# Pan_Tilt_Stepper_Control.net
KiCad netlist of a schematic drawn in Altium Designer
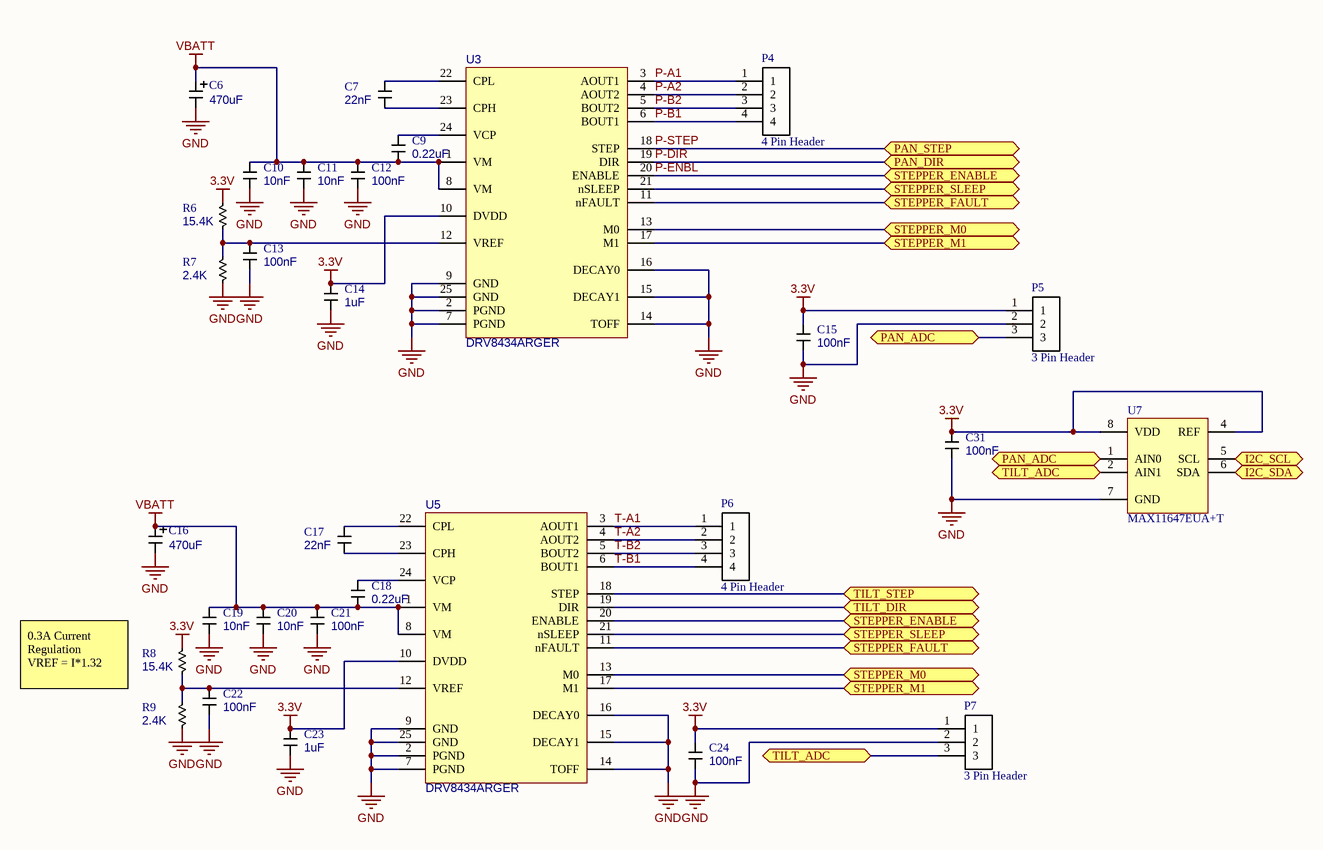
[diagram p0: Pan & Tilt Stepper Control.SchDoc]

(export (version "E")
  (design (tool "Eeschema 10.0.6"))
  (components
    (comp (ref "C6")
      (value "F")
      (footprint "Panasonic EEE-FT1E471AP")
      (description "Polarized Capacitor")
      (fields
        (field (name "MANUFACTURER") "Panasonic Electronic Components")
        (field (name "MANUFACTURER PART NUMBER") "EEE-FT1E471AP")
        (field (name "CAPACITANCE") "470uF")
      )
      (libsource (lib "Rigby Electronics Schematic Library") (part "Capacitor Polarized"))
    )
    (comp (ref "C7")
      (value "F")
      (footprint "C0805")
      (description "Capacitor")
      (fields
        (field (name "MANUFACTURER") "TDK Corporation")
        (field (name "MANUFACTURER PART NUMBER") "CGA4J3X7R2E223K125AA")
        (field (name "CAPACITANCE") "22nF")
      )
      (libsource (lib "Rigby Electronics Schematic Library") (part "Capacitor"))
    )
    (comp (ref "C9")
      (value "F")
      (footprint "C0805")
      (description "Capacitor")
      (fields
        (field (name "MANUFACTURER") "KEMET")
        (field (name "MANUFACTURER PART NUMBER") "C0805C224K5RAC7800")
        (field (name "CAPACITANCE") "0.22uF")
      )
      (libsource (lib "Rigby Electronics Schematic Library") (part "Capacitor"))
    )
    (comp (ref "C10")
      (value "F")
      (footprint "C0805")
      (description "Capacitor")
      (fields
        (field (name "MANUFACTURER") "YAGEO")
        (field (name "MANUFACTURER PART NUMBER") "CC0805KRX7R9BB103")
        (field (name "CAPACITANCE") "10nF")
      )
      (libsource (lib "Rigby Electronics Schematic Library") (part "Capacitor"))
    )
    (comp (ref "C11")
      (value "F")
      (footprint "C0805")
      (description "Capacitor")
      (fields
        (field (name "MANUFACTURER") "YAGEO")
        (field (name "MANUFACTURER PART NUMBER") "CC0805KRX7R9BB103")
        (field (name "CAPACITANCE") "10nF")
      )
      (libsource (lib "Rigby Electronics Schematic Library") (part "Capacitor"))
    )
    (comp (ref "C12")
      (value "F")
      (footprint "C0805")
      (description "Capacitor")
      (fields
        (field (name "MANUFACTURER") "Samsung Electro-Mechanics")
        (field (name "MANUFACTURER PART NUMBER") "CL21B104KBCNNNC")
        (field (name "CAPACITANCE") "100nF")
      )
      (libsource (lib "Rigby Electronics Schematic Library") (part "Capacitor"))
    )
    (comp (ref "C13")
      (value "F")
      (footprint "C0805")
      (description "Capacitor")
      (fields
        (field (name "MANUFACTURER") "Samsung Electro-Mechanics")
        (field (name "MANUFACTURER PART NUMBER") "CL21B104KBCNNNC")
        (field (name "CAPACITANCE") "100nF")
      )
      (libsource (lib "Rigby Electronics Schematic Library") (part "Capacitor"))
    )
    (comp (ref "C14")
      (value "F")
      (footprint "C0805")
      (description "Capacitor")
      (fields
        (field (name "MANUFACTURER") "Samsung Electro-Mechanics")
        (field (name "MANUFACTURER PART NUMBER") "CL21B105KAFNNNE")
        (field (name "CAPACITANCE") "1uF")
      )
      (libsource (lib "Rigby Electronics Schematic Library") (part "Capacitor"))
    )
    (comp (ref "C15")
      (value "F")
      (footprint "C0805")
      (description "Capacitor")
      (fields
        (field (name "MANUFACTURER") "Samsung Electro-Mechanics")
        (field (name "MANUFACTURER PART NUMBER") "CL21B104KBCNNNC")
        (field (name "CAPACITANCE") "100nF")
      )
      (libsource (lib "Rigby Electronics Schematic Library") (part "Capacitor"))
    )
    (comp (ref "C16")
      (value "F")
      (footprint "Panasonic EEE-FT1E471AP")
      (description "Polarized Capacitor")
      (fields
        (field (name "MANUFACTURER") "Panasonic Electronic Components")
        (field (name "MANUFACTURER PART NUMBER") "EEE-FT1E471AP")
        (field (name "CAPACITANCE") "470uF")
      )
      (libsource (lib "Rigby Electronics Schematic Library") (part "Capacitor Polarized"))
    )
    (comp (ref "C17")
      (value "F")
      (footprint "C0805")
      (description "Capacitor")
      (fields
        (field (name "MANUFACTURER") "TDK Corporation")
        (field (name "MANUFACTURER PART NUMBER") "CGA4J3X7R2E223K125AA")
        (field (name "CAPACITANCE") "22nF")
      )
      (libsource (lib "Rigby Electronics Schematic Library") (part "Capacitor"))
    )
    (comp (ref "C18")
      (value "F")
      (footprint "C0805")
      (description "Capacitor")
      (fields
        (field (name "MANUFACTURER") "KEMET")
        (field (name "MANUFACTURER PART NUMBER") "C0805C224K5RAC7800")
        (field (name "CAPACITANCE") "0.22uF")
      )
      (libsource (lib "Rigby Electronics Schematic Library") (part "Capacitor"))
    )
    (comp (ref "C19")
      (value "F")
      (footprint "C0805")
      (description "Capacitor")
      (fields
        (field (name "MANUFACTURER") "YAGEO")
        (field (name "MANUFACTURER PART NUMBER") "CC0805KRX7R9BB103")
        (field (name "CAPACITANCE") "10nF")
      )
      (libsource (lib "Rigby Electronics Schematic Library") (part "Capacitor"))
    )
    (comp (ref "C20")
      (value "F")
      (footprint "C0805")
      (description "Capacitor")
      (fields
        (field (name "MANUFACTURER") "YAGEO")
        (field (name "MANUFACTURER PART NUMBER") "CC0805KRX7R9BB103")
        (field (name "CAPACITANCE") "10nF")
      )
      (libsource (lib "Rigby Electronics Schematic Library") (part "Capacitor"))
    )
    (comp (ref "C21")
      (value "F")
      (footprint "C0805")
      (description "Capacitor")
      (fields
        (field (name "MANUFACTURER") "Samsung Electro-Mechanics")
        (field (name "MANUFACTURER PART NUMBER") "CL21B104KBCNNNC")
        (field (name "CAPACITANCE") "100nF")
      )
      (libsource (lib "Rigby Electronics Schematic Library") (part "Capacitor"))
    )
    (comp (ref "C22")
      (value "F")
      (footprint "C0805")
      (description "Capacitor")
      (fields
        (field (name "MANUFACTURER") "Samsung Electro-Mechanics")
        (field (name "MANUFACTURER PART NUMBER") "CL21B104KBCNNNC")
        (field (name "CAPACITANCE") "100nF")
      )
      (libsource (lib "Rigby Electronics Schematic Library") (part "Capacitor"))
    )
    (comp (ref "C23")
      (value "F")
      (footprint "C0805")
      (description "Capacitor")
      (fields
        (field (name "MANUFACTURER") "Samsung Electro-Mechanics")
        (field (name "MANUFACTURER PART NUMBER") "CL21B105KAFNNNE")
        (field (name "CAPACITANCE") "1uF")
      )
      (libsource (lib "Rigby Electronics Schematic Library") (part "Capacitor"))
    )
    (comp (ref "C24")
      (value "F")
      (footprint "C0805")
      (description "Capacitor")
      (fields
        (field (name "MANUFACTURER") "Samsung Electro-Mechanics")
        (field (name "MANUFACTURER PART NUMBER") "CL21B104KBCNNNC")
        (field (name "CAPACITANCE") "100nF")
      )
      (libsource (lib "Rigby Electronics Schematic Library") (part "Capacitor"))
    )
    (comp (ref "C31")
      (value "F")
      (footprint "C0805")
      (description "Capacitor")
      (fields
        (field (name "MANUFACTURER") "Samsung Electro-Mechanics")
        (field (name "MANUFACTURER PART NUMBER") "CL21B104KBCNNNC")
        (field (name "CAPACITANCE") "100nF")
      )
      (libsource (lib "Rigby Electronics Schematic Library") (part "Capacitor"))
    )
    (comp (ref "P4")
      (value "4 Pin Header")
      (footprint "B4B-XH-A")
      (fields (field (name "MANUFACTURER") "JST") (field (name "MANUFACTURER PART NUMBER") "B4B-XH-2"))
      (libsource (lib "Rigby Electronics Schematic Library") (part "Header 4"))
    )
    (comp (ref "P5")
      (value "3 Pin Header")
      (footprint "B3B-XH-A")
      (fields
        (field (name "MANUFACTURER") "JST Sales America Inc.")
        (field (name "MANUFACTURER PART NUMBER") "B3B-XH-A")
      )
      (libsource (lib "Rigby Electronics Library") (part "Header 3"))
    )
    (comp (ref "P6")
      (value "4 Pin Header")
      (footprint "B4B-XH-A")
      (fields (field (name "MANUFACTURER") "JST") (field (name "MANUFACTURER PART NUMBER") "B4B-XH-2"))
      (libsource (lib "Rigby Electronics Schematic Library") (part "Header 4"))
    )
    (comp (ref "P7")
      (value "3 Pin Header")
      (footprint "B3B-XH-A")
      (fields
        (field (name "MANUFACTURER") "JST Sales America Inc.")
        (field (name "MANUFACTURER PART NUMBER") "B3B-XH-A")
      )
      (libsource (lib "Rigby Electronics Library") (part "Header 3"))
    )
    (comp (ref "R6")
      (value "330Ω")
      (footprint "R0805")
      (description "Standard Resistor")
      (fields
        (field (name "MANUFACTURER") "Vishay Dale")
        (field (name "MANUFACTURER PART NUMBER") "CRCW080515K4FKEA")
        (field (name "RESISTANCE") "15.4K")
      )
      (libsource (lib "Rigby Electronics Schematic Library") (part "Resistor"))
    )
    (comp (ref "R7")
      (value "330Ω")
      (footprint "R0805")
      (description "Standard Resistor")
      (fields
        (field (name "MANUFACTURER") "Vishay Dale")
        (field (name "MANUFACTURER PART NUMBER") "CRCW08052K10FKEA")
        (field (name "RESISTANCE") "2.4K")
      )
      (libsource (lib "Rigby Electronics Schematic Library") (part "Resistor"))
    )
    (comp (ref "R8")
      (value "330Ω")
      (footprint "R0805")
      (description "Standard Resistor")
      (fields
        (field (name "MANUFACTURER") "Vishay Dale")
        (field (name "MANUFACTURER PART NUMBER") "CRCW080515K4FKEA")
        (field (name "RESISTANCE") "15.4K")
      )
      (libsource (lib "Rigby Electronics Schematic Library") (part "Resistor"))
    )
    (comp (ref "R9")
      (value "330Ω")
      (footprint "R0805")
      (description "Standard Resistor")
      (fields
        (field (name "MANUFACTURER") "Vishay Dale")
        (field (name "MANUFACTURER PART NUMBER") "CRCW08052K10FKEA")
        (field (name "RESISTANCE") "2.4K")
      )
      (libsource (lib "Rigby Electronics Schematic Library") (part "Resistor"))
    )
    (comp (ref "U3")
      (value "DRV8434ARGER")
      (footprint "DRV8434ARGER")
      (description "Bipolar Motor Driver NMOS Step/Direction 24-VQFN (4x4)")
      (fields (field (name "MANUFACTURER") "Texas Instruments"))
      (libsource (lib "Rigby Electronics Schematic Library") (part "DRV8434ARGER"))
    )
    (comp (ref "U5")
      (value "DRV8434ARGER")
      (footprint "DRV8434ARGER")
      (description "Bipolar Motor Driver NMOS Step/Direction 24-VQFN (4x4)")
      (fields (field (name "MANUFACTURER") "Texas Instruments"))
      (libsource (lib "Rigby Electronics Schematic Library") (part "DRV8434ARGER"))
    )
    (comp (ref "U7")
      (value "MAX11647EUA+T")
      (footprint "MAX11647EUA+T")
      (description "10 Bit Analog to Digital Converter 1, 2 Input 1 SAR 8-uMAX/uSOP")
      (fields (field (name "MANUFACTURER") "Analog Devices Inc./Maxim Integrated"))
      (libsource (lib "Rigby Electronics Schematic Library") (part "MAX11647EUA+T"))
    )
  )
  (nets
    (net (code "1") (name "/I2C_SCL") (class "Default")
      (node (ref "U7") (pin "5") (pinfunction "SCL_5") (pintype "passive"))
    )
    (net (code "2") (name "/I2C_SDA") (class "Default")
      (node (ref "U7") (pin "6") (pinfunction "SDA_6") (pintype "passive"))
    )
    (net (code "3") (name "/P-A1") (class "Default")
      (node (ref "P4") (pin "1") (pinfunction "1_1") (pintype "passive"))
      (node (ref "U3") (pin "3") (pinfunction "AOUT1_3") (pintype "passive"))
    )
    (net (code "4") (name "/P-A2") (class "Default")
      (node (ref "P4") (pin "2") (pinfunction "2_2") (pintype "passive"))
      (node (ref "U3") (pin "4") (pinfunction "AOUT2_4") (pintype "passive"))
    )
    (net (code "5") (name "/P-B1") (class "Default")
      (node (ref "P4") (pin "4") (pinfunction "4_4") (pintype "passive"))
      (node (ref "U3") (pin "6") (pinfunction "BOUT1_6") (pintype "passive"))
    )
    (net (code "6") (name "/P-B2") (class "Default")
      (node (ref "P4") (pin "3") (pinfunction "3_3") (pintype "passive"))
      (node (ref "U3") (pin "5") (pinfunction "BOUT2_5") (pintype "passive"))
    )
    (net (code "7") (name "/P-DIR") (class "Default")
      (node (ref "U3") (pin "19") (pinfunction "DIR_19") (pintype "passive"))
    )
    (net (code "8") (name "/P-ENBL") (class "Default")
      (node (ref "U3") (pin "20") (pinfunction "ENABLE_20") (pintype "passive"))
      (node (ref "U5") (pin "20") (pinfunction "ENABLE_20") (pintype "passive"))
    )
    (net (code "9") (name "/P-STEP") (class "Default")
      (node (ref "U3") (pin "18") (pinfunction "STEP_18") (pintype "passive"))
    )
    (net (code "10") (name "/PAN_ADC") (class "Default")
      (node (ref "P5") (pin "3") (pinfunction "3_3") (pintype "passive"))
      (node (ref "U7") (pin "1") (pinfunction "AIN0_1") (pintype "passive"))
    )
    (net (code "11") (name "/STEPPER_FAULT") (class "Default")
      (node (ref "U3") (pin "11") (pinfunction "nFAULT_11") (pintype "passive"))
      (node (ref "U5") (pin "11") (pinfunction "nFAULT_11") (pintype "passive"))
    )
    (net (code "12") (name "/STEPPER_M0") (class "Default")
      (node (ref "U3") (pin "13") (pinfunction "M0_13") (pintype "passive"))
      (node (ref "U5") (pin "13") (pinfunction "M0_13") (pintype "passive"))
    )
    (net (code "13") (name "/STEPPER_M1") (class "Default")
      (node (ref "U3") (pin "17") (pinfunction "M1_17") (pintype "passive"))
      (node (ref "U5") (pin "17") (pinfunction "M1_17") (pintype "passive"))
    )
    (net (code "14") (name "/STEPPER_SLEEP") (class "Default")
      (node (ref "U3") (pin "21") (pinfunction "nSLEEP_21") (pintype "passive"))
      (node (ref "U5") (pin "21") (pinfunction "nSLEEP_21") (pintype "passive"))
    )
    (net (code "15") (name "/T-A1") (class "Default")
      (node (ref "P6") (pin "1") (pinfunction "1_1") (pintype "passive"))
      (node (ref "U5") (pin "3") (pinfunction "AOUT1_3") (pintype "passive"))
    )
    (net (code "16") (name "/T-A2") (class "Default")
      (node (ref "P6") (pin "2") (pinfunction "2_2") (pintype "passive"))
      (node (ref "U5") (pin "4") (pinfunction "AOUT2_4") (pintype "passive"))
    )
    (net (code "17") (name "/T-B1") (class "Default")
      (node (ref "P6") (pin "4") (pinfunction "4_4") (pintype "passive"))
      (node (ref "U5") (pin "6") (pinfunction "BOUT1_6") (pintype "passive"))
    )
    (net (code "18") (name "/T-B2") (class "Default")
      (node (ref "P6") (pin "3") (pinfunction "3_3") (pintype "passive"))
      (node (ref "U5") (pin "5") (pinfunction "BOUT2_5") (pintype "passive"))
    )
    (net (code "19") (name "/TILT_ADC") (class "Default")
      (node (ref "P7") (pin "3") (pinfunction "3_3") (pintype "passive"))
      (node (ref "U7") (pin "2") (pinfunction "AIN1_2") (pintype "passive"))
    )
    (net (code "20") (name "/TILT_DIR") (class "Default")
      (node (ref "U5") (pin "19") (pinfunction "DIR_19") (pintype "passive"))
    )
    (net (code "21") (name "/TILT_STEP") (class "Default")
      (node (ref "U5") (pin "18") (pinfunction "STEP_18") (pintype "passive"))
    )
    (net (code "22") (name "3.3V") (class "Default")
      (node (ref "C14") (pin "1") (pinfunction "1_1") (pintype "passive"))
      (node (ref "C15") (pin "1") (pinfunction "1_1") (pintype "passive"))
      (node (ref "C23") (pin "1") (pinfunction "1_1") (pintype "passive"))
      (node (ref "C24") (pin "1") (pinfunction "1_1") (pintype "passive"))
      (node (ref "C31") (pin "1") (pinfunction "1_1") (pintype "passive"))
      (node (ref "P5") (pin "1") (pinfunction "1_1") (pintype "passive"))
      (node (ref "P7") (pin "1") (pinfunction "1_1") (pintype "passive"))
      (node (ref "R6") (pin "2") (pinfunction "2_2") (pintype "passive"))
      (node (ref "R8") (pin "2") (pinfunction "2_2") (pintype "passive"))
      (node (ref "U3") (pin "10") (pinfunction "DVDD_10") (pintype "passive"))
      (node (ref "U5") (pin "10") (pinfunction "DVDD_10") (pintype "passive"))
      (node (ref "U7") (pin "4") (pinfunction "REF_4") (pintype "passive"))
      (node (ref "U7") (pin "8") (pinfunction "VDD_8") (pintype "passive"))
    )
    (net (code "23") (name "GND") (class "Default")
      (node (ref "C10") (pin "2") (pinfunction "2_2") (pintype "passive"))
      (node (ref "C11") (pin "2") (pinfunction "2_2") (pintype "passive"))
      (node (ref "C12") (pin "2") (pinfunction "2_2") (pintype "passive"))
      (node (ref "C13") (pin "2") (pinfunction "2_2") (pintype "passive"))
      (node (ref "C14") (pin "2") (pinfunction "2_2") (pintype "passive"))
      (node (ref "C15") (pin "2") (pinfunction "2_2") (pintype "passive"))
      (node (ref "C16") (pin "2") (pinfunction "2_2") (pintype "passive"))
      (node (ref "C19") (pin "2") (pinfunction "2_2") (pintype "passive"))
      (node (ref "C20") (pin "2") (pinfunction "2_2") (pintype "passive"))
      (node (ref "C21") (pin "2") (pinfunction "2_2") (pintype "passive"))
      (node (ref "C22") (pin "2") (pinfunction "2_2") (pintype "passive"))
      (node (ref "C23") (pin "2") (pinfunction "2_2") (pintype "passive"))
      (node (ref "C24") (pin "2") (pinfunction "2_2") (pintype "passive"))
      (node (ref "C31") (pin "2") (pinfunction "2_2") (pintype "passive"))
      (node (ref "C6") (pin "2") (pinfunction "2_2") (pintype "passive"))
      (node (ref "P5") (pin "2") (pinfunction "2_2") (pintype "passive"))
      (node (ref "P7") (pin "2") (pinfunction "2_2") (pintype "passive"))
      (node (ref "R7") (pin "1") (pinfunction "1_1") (pintype "passive"))
      (node (ref "R9") (pin "1") (pinfunction "1_1") (pintype "passive"))
      (node (ref "U3") (pin "14") (pinfunction "TOFF_14") (pintype "passive"))
      (node (ref "U3") (pin "15") (pinfunction "DECAY1_15") (pintype "passive"))
      (node (ref "U3") (pin "16") (pinfunction "DECAY0_16") (pintype "passive"))
      (node (ref "U3") (pin "2") (pinfunction "PGND_2") (pintype "passive"))
      (node (ref "U3") (pin "25") (pinfunction "GND_25") (pintype "passive"))
      (node (ref "U3") (pin "7") (pinfunction "PGND_7") (pintype "passive"))
      (node (ref "U3") (pin "9") (pinfunction "GND_9") (pintype "passive"))
      (node (ref "U5") (pin "14") (pinfunction "TOFF_14") (pintype "passive"))
      (node (ref "U5") (pin "15") (pinfunction "DECAY1_15") (pintype "passive"))
      (node (ref "U5") (pin "16") (pinfunction "DECAY0_16") (pintype "passive"))
      (node (ref "U5") (pin "2") (pinfunction "PGND_2") (pintype "passive"))
      (node (ref "U5") (pin "25") (pinfunction "GND_25") (pintype "passive"))
      (node (ref "U5") (pin "7") (pinfunction "PGND_7") (pintype "passive"))
      (node (ref "U5") (pin "9") (pinfunction "GND_9") (pintype "passive"))
      (node (ref "U7") (pin "7") (pinfunction "GND_7") (pintype "passive"))
    )
    (net (code "24") (name "Net-(U3-CPH)") (class "Default")
      (node (ref "C7") (pin "2") (pinfunction "2_2") (pintype "passive"))
      (node (ref "U3") (pin "23") (pinfunction "CPH_23") (pintype "passive"))
    )
    (net (code "25") (name "Net-(U3-CPL)") (class "Default")
      (node (ref "C7") (pin "1") (pinfunction "1_1") (pintype "passive"))
      (node (ref "U3") (pin "22") (pinfunction "CPL_22") (pintype "passive"))
    )
    (net (code "26") (name "Net-(U3-VCP)") (class "Default")
      (node (ref "C9") (pin "1") (pinfunction "1_1") (pintype "passive"))
      (node (ref "U3") (pin "24") (pinfunction "VCP_24") (pintype "passive"))
    )
    (net (code "27") (name "Net-(U3-VREF)") (class "Default")
      (node (ref "C13") (pin "1") (pinfunction "1_1") (pintype "passive"))
      (node (ref "R6") (pin "1") (pinfunction "1_1") (pintype "passive"))
      (node (ref "R7") (pin "2") (pinfunction "2_2") (pintype "passive"))
      (node (ref "U3") (pin "12") (pinfunction "VREF_12") (pintype "passive"))
    )
    (net (code "28") (name "Net-(U5-CPH)") (class "Default")
      (node (ref "C17") (pin "2") (pinfunction "2_2") (pintype "passive"))
      (node (ref "U5") (pin "23") (pinfunction "CPH_23") (pintype "passive"))
    )
    (net (code "29") (name "Net-(U5-CPL)") (class "Default")
      (node (ref "C17") (pin "1") (pinfunction "1_1") (pintype "passive"))
      (node (ref "U5") (pin "22") (pinfunction "CPL_22") (pintype "passive"))
    )
    (net (code "30") (name "Net-(U5-VCP)") (class "Default")
      (node (ref "C18") (pin "1") (pinfunction "1_1") (pintype "passive"))
      (node (ref "U5") (pin "24") (pinfunction "VCP_24") (pintype "passive"))
    )
    (net (code "31") (name "Net-(U5-VREF)") (class "Default")
      (node (ref "C22") (pin "1") (pinfunction "1_1") (pintype "passive"))
      (node (ref "R8") (pin "1") (pinfunction "1_1") (pintype "passive"))
      (node (ref "R9") (pin "2") (pinfunction "2_2") (pintype "passive"))
      (node (ref "U5") (pin "12") (pinfunction "VREF_12") (pintype "passive"))
    )
    (net (code "32") (name "VBATT") (class "Default")
      (node (ref "C10") (pin "1") (pinfunction "1_1") (pintype "passive"))
      (node (ref "C11") (pin "1") (pinfunction "1_1") (pintype "passive"))
      (node (ref "C12") (pin "1") (pinfunction "1_1") (pintype "passive"))
      (node (ref "C16") (pin "1") (pinfunction "1_1") (pintype "passive"))
      (node (ref "C18") (pin "2") (pinfunction "2_2") (pintype "passive"))
      (node (ref "C19") (pin "1") (pinfunction "1_1") (pintype "passive"))
      (node (ref "C20") (pin "1") (pinfunction "1_1") (pintype "passive"))
      (node (ref "C21") (pin "1") (pinfunction "1_1") (pintype "passive"))
      (node (ref "C6") (pin "1") (pinfunction "1_1") (pintype "passive"))
      (node (ref "C9") (pin "2") (pinfunction "2_2") (pintype "passive"))
      (node (ref "U3") (pin "1") (pinfunction "VM_1") (pintype "passive"))
      (node (ref "U3") (pin "8") (pinfunction "VM_8") (pintype "passive"))
      (node (ref "U5") (pin "1") (pinfunction "VM_1") (pintype "passive"))
      (node (ref "U5") (pin "8") (pinfunction "VM_8") (pintype "passive"))
    )
  )
)
